# Wattuino-Nanite85_v11.net
KiCad netlist of a schematic drawn in EAGLE
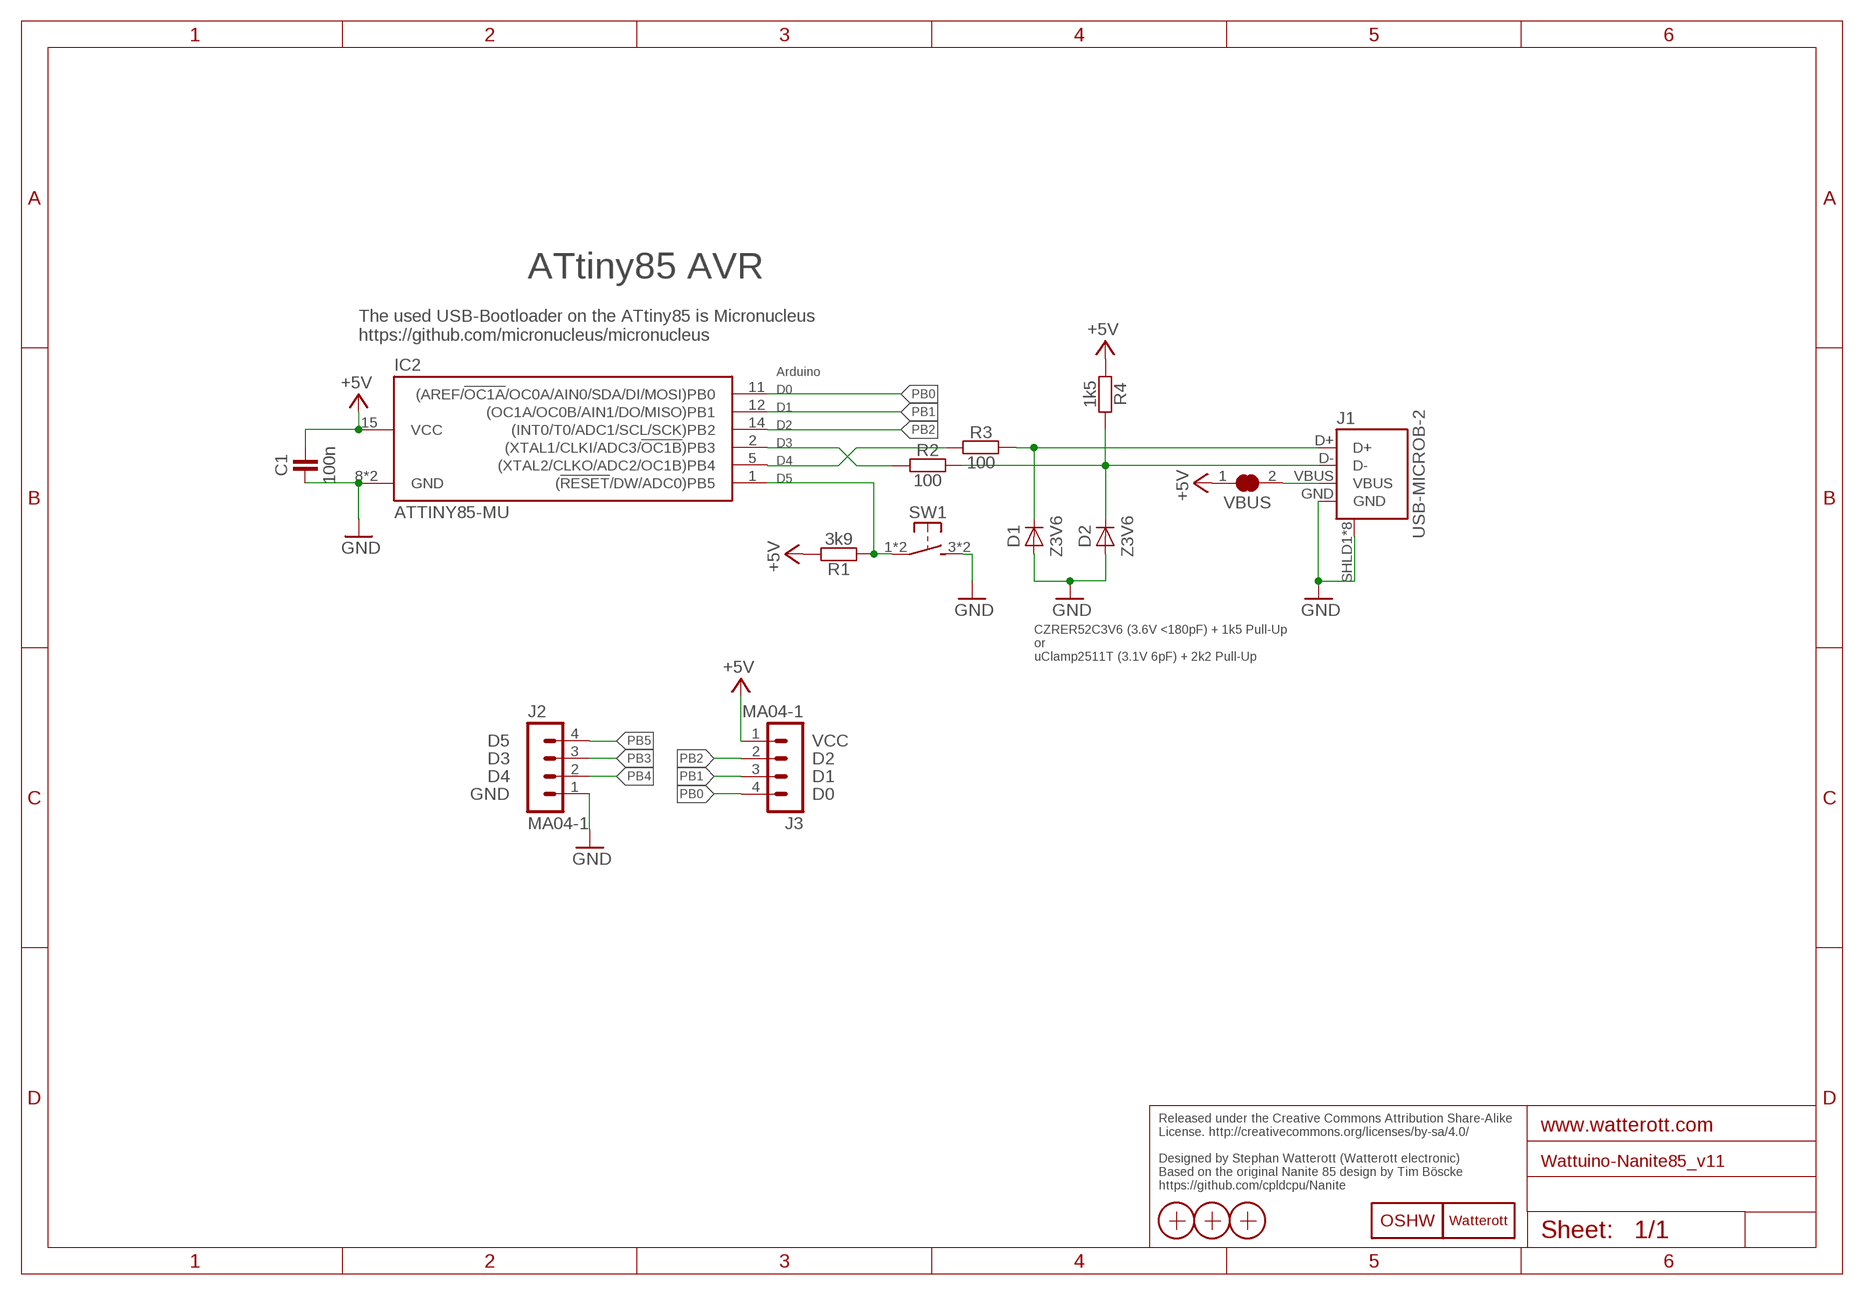
[diagram p0: schematic, sheet 1]

(export (version "E")
  (design (tool "Eeschema 10.0.6"))
  (components
    (comp (ref "C1")
      (value "100n")
      (footprint "eagle-import:C0402")
      (libsource (lib "eagle-import") (part "CAPACITOR-0402"))
    )
    (comp (ref "D1")
      (value "Z3V6")
      (footprint "eagle-import:SOD882")
      (libsource (lib "eagle-import") (part "DIODE-SOD882"))
    )
    (comp (ref "D2")
      (value "Z3V6")
      (footprint "eagle-import:SOD882")
      (libsource (lib "eagle-import") (part "DIODE-SOD882"))
    )
    (comp (ref "IC2")
      (value "ATTINY85-MU")
      (footprint "eagle-import:QFN20-PAD")
      (libsource (lib "eagle-import") (part "ATTINY85-MU"))
    )
    (comp (ref "J1")
      (value "USB-MICROB-2")
      (footprint "eagle-import:USB-MICROB-10118194")
      (libsource (lib "eagle-import") (part "USB-MICROB-2"))
    )
    (comp (ref "J2")
      (value "MA04-1")
      (footprint "eagle-import:MA04-1")
      (libsource (lib "eagle-import") (part "MA04-1"))
    )
    (comp (ref "J3")
      (value "MA04-1")
      (footprint "eagle-import:MA04-1")
      (libsource (lib "eagle-import") (part "MA04-1"))
    )
    (comp (ref "LOGO1")
      (value "LOGO-S_PLACE_S")
      (footprint "eagle-import:SPARK_TPLACE_S")
      (libsource (lib "eagle-import") (part "LOGO-S_PLACE_S"))
    )
    (comp (ref "LOGO2")
      (value "OSHW_LOGOX0070")
      (footprint "eagle-import:OSHW_6X70")
      (libsource (lib "eagle-import") (part "OSHW_LOGOX0070"))
    )
    (comp (ref "R1")
      (value "3k9")
      (footprint "eagle-import:C0402")
      (libsource (lib "eagle-import") (part "RESISTOR-0402"))
    )
    (comp (ref "R2")
      (value "100")
      (footprint "eagle-import:C0402")
      (libsource (lib "eagle-import") (part "RESISTOR-0402"))
    )
    (comp (ref "R3")
      (value "100")
      (footprint "eagle-import:C0402")
      (libsource (lib "eagle-import") (part "RESISTOR-0402"))
    )
    (comp (ref "R4")
      (value "1k5")
      (footprint "eagle-import:C0402")
      (libsource (lib "eagle-import") (part "RESISTOR-0402"))
    )
    (comp (ref "SW1")
      (value "SW-TACTILE-PTS840P")
      (footprint "eagle-import:PTS840P")
      (libsource (lib "eagle-import") (part "SW-TACTILE-PTS840P"))
    )
    (comp (ref "VBUS")
      (value "JUMPER2-0603-NC")
      (footprint "eagle-import:JUMPER2-0603_NC")
      (libsource (lib "eagle-import") (part "JUMPER2-0603-NC"))
    )
    (comp (ref "X1")
      (value "PASSER-07")
      (footprint "eagle-import:PASSER_07MM")
      (libsource (lib "eagle-import") (part "PASSER-07"))
    )
    (comp (ref "X2")
      (value "PASSER-07")
      (footprint "eagle-import:PASSER_07MM")
      (libsource (lib "eagle-import") (part "PASSER-07"))
    )
    (comp (ref "X3")
      (value "PASSER-07")
      (footprint "eagle-import:PASSER_07MM")
      (libsource (lib "eagle-import") (part "PASSER-07"))
    )
  )
  (nets
    (net (code "1") (name "+5V") (class "Default")
      (node (ref "C1") (pin "2") (pinfunction "2_2") (pintype "passive"))
      (node (ref "IC2") (pin "15") (pinfunction "VCC_15") (pintype "power_in"))
      (node (ref "J3") (pin "1") (pinfunction "1_1") (pintype "passive"))
      (node (ref "R1") (pin "2") (pinfunction "2_2") (pintype "passive"))
      (node (ref "R4") (pin "1") (pinfunction "1_1") (pintype "passive"))
      (node (ref "VBUS") (pin "1") (pinfunction "1_1") (pintype "passive"))
    )
    (net (code "2") (name "GND") (class "Default")
      (node (ref "C1") (pin "1") (pinfunction "1_1") (pintype "passive"))
      (node (ref "D1") (pin "A") (pinfunction "A_A") (pintype "passive"))
      (node (ref "D2") (pin "A") (pinfunction "A_A") (pintype "passive"))
      (node (ref "IC2") (pin "8") (pinfunction "GND_8") (pintype "power_in"))
      (node (ref "IC2") (pin "TP") (pinfunction "GND_TP") (pintype "power_in"))
      (node (ref "J1") (pin "GND") (pinfunction "GND_GND") (pintype "power_in"))
      (node (ref "J1") (pin "SHLD1") (pinfunction "SHIELD_SHLD1") (pintype "passive"))
      (node (ref "J1") (pin "SHLD2") (pinfunction "SHIELD_SHLD2") (pintype "passive"))
      (node (ref "J1") (pin "SHLD3") (pinfunction "SHIELD_SHLD3") (pintype "passive"))
      (node (ref "J1") (pin "SHLD4") (pinfunction "SHIELD_SHLD4") (pintype "passive"))
      (node (ref "J1") (pin "SHLD5") (pinfunction "SHIELD_SHLD5") (pintype "passive"))
      (node (ref "J1") (pin "SHLD6") (pinfunction "SHIELD_SHLD6") (pintype "passive"))
      (node (ref "J1") (pin "SHLD7") (pinfunction "SHIELD_SHLD7") (pintype "passive"))
      (node (ref "J1") (pin "SHLD8") (pinfunction "SHIELD_SHLD8") (pintype "passive"))
      (node (ref "J2") (pin "1") (pinfunction "1_1") (pintype "passive"))
      (node (ref "SW1") (pin "3") (pinfunction "S1_3") (pintype "passive"))
      (node (ref "SW1") (pin "4") (pinfunction "S1_4") (pintype "passive"))
    )
    (net (code "3") (name "Net-(D1-PadC)") (class "Default")
      (node (ref "D1") (pin "C") (pinfunction "C_C") (pintype "passive"))
      (node (ref "J1") (pin "D+") (pinfunction "D+_D+") (pintype "bidirectional"))
      (node (ref "R3") (pin "2") (pinfunction "2_2") (pintype "passive"))
    )
    (net (code "4") (name "Net-(D2-PadC)") (class "Default")
      (node (ref "D2") (pin "C") (pinfunction "C_C") (pintype "passive"))
      (node (ref "J1") (pin "D-") (pinfunction "D-_D-") (pintype "bidirectional"))
      (node (ref "R2") (pin "2") (pinfunction "2_2") (pintype "passive"))
      (node (ref "R4") (pin "2") (pinfunction "2_2") (pintype "passive"))
    )
    (net (code "5") (name "Net-(J1-PadVBUS)") (class "Default")
      (node (ref "J1") (pin "VBUS") (pinfunction "VBUS_VBUS") (pintype "power_in"))
      (node (ref "VBUS") (pin "2") (pinfunction "2_2") (pintype "passive"))
    )
    (net (code "6") (name "PB0") (class "Default")
      (node (ref "IC2") (pin "11") (pinfunction "(AREF/~{OC1A}/OC0A/AIN0/SDA/DI/MOSI)PB0_11") (pintype "bidirectional"))
      (node (ref "J3") (pin "4") (pinfunction "4_4") (pintype "passive"))
    )
    (net (code "7") (name "PB1") (class "Default")
      (node (ref "IC2") (pin "12") (pinfunction "(OC1A/OC0B/AIN1/DO/MISO)PB1_12") (pintype "bidirectional"))
      (node (ref "J3") (pin "3") (pinfunction "3_3") (pintype "passive"))
    )
    (net (code "8") (name "PB2") (class "Default")
      (node (ref "IC2") (pin "14") (pinfunction "(INT0/T0/ADC1/SCL/SCK)PB2_14") (pintype "bidirectional"))
      (node (ref "J3") (pin "2") (pinfunction "2_2") (pintype "passive"))
    )
    (net (code "9") (name "PB3") (class "Default")
      (node (ref "IC2") (pin "2") (pinfunction "(XTAL1/CLKI/ADC3/~{OC1B})PB3_2") (pintype "bidirectional"))
      (node (ref "J2") (pin "3") (pinfunction "3_3") (pintype "passive"))
      (node (ref "R2") (pin "1") (pinfunction "1_1") (pintype "passive"))
    )
    (net (code "10") (name "PB4") (class "Default")
      (node (ref "IC2") (pin "5") (pinfunction "(XTAL2/CLKO/ADC2/OC1B)PB4_5") (pintype "bidirectional"))
      (node (ref "J2") (pin "2") (pinfunction "2_2") (pintype "passive"))
      (node (ref "R3") (pin "1") (pinfunction "1_1") (pintype "passive"))
    )
    (net (code "11") (name "PB5") (class "Default")
      (node (ref "IC2") (pin "1") (pinfunction "(~{RESET}/DW/ADC0)PB5_1") (pintype "bidirectional"))
      (node (ref "J2") (pin "4") (pinfunction "4_4") (pintype "passive"))
      (node (ref "R1") (pin "1") (pinfunction "1_1") (pintype "passive"))
      (node (ref "SW1") (pin "1") (pinfunction "P1_1") (pintype "passive"))
      (node (ref "SW1") (pin "2") (pinfunction "P1_2") (pintype "passive"))
    )
  )
)
